# cpu_nand.net
KiCad netlist of a schematic drawn in Altium Designer
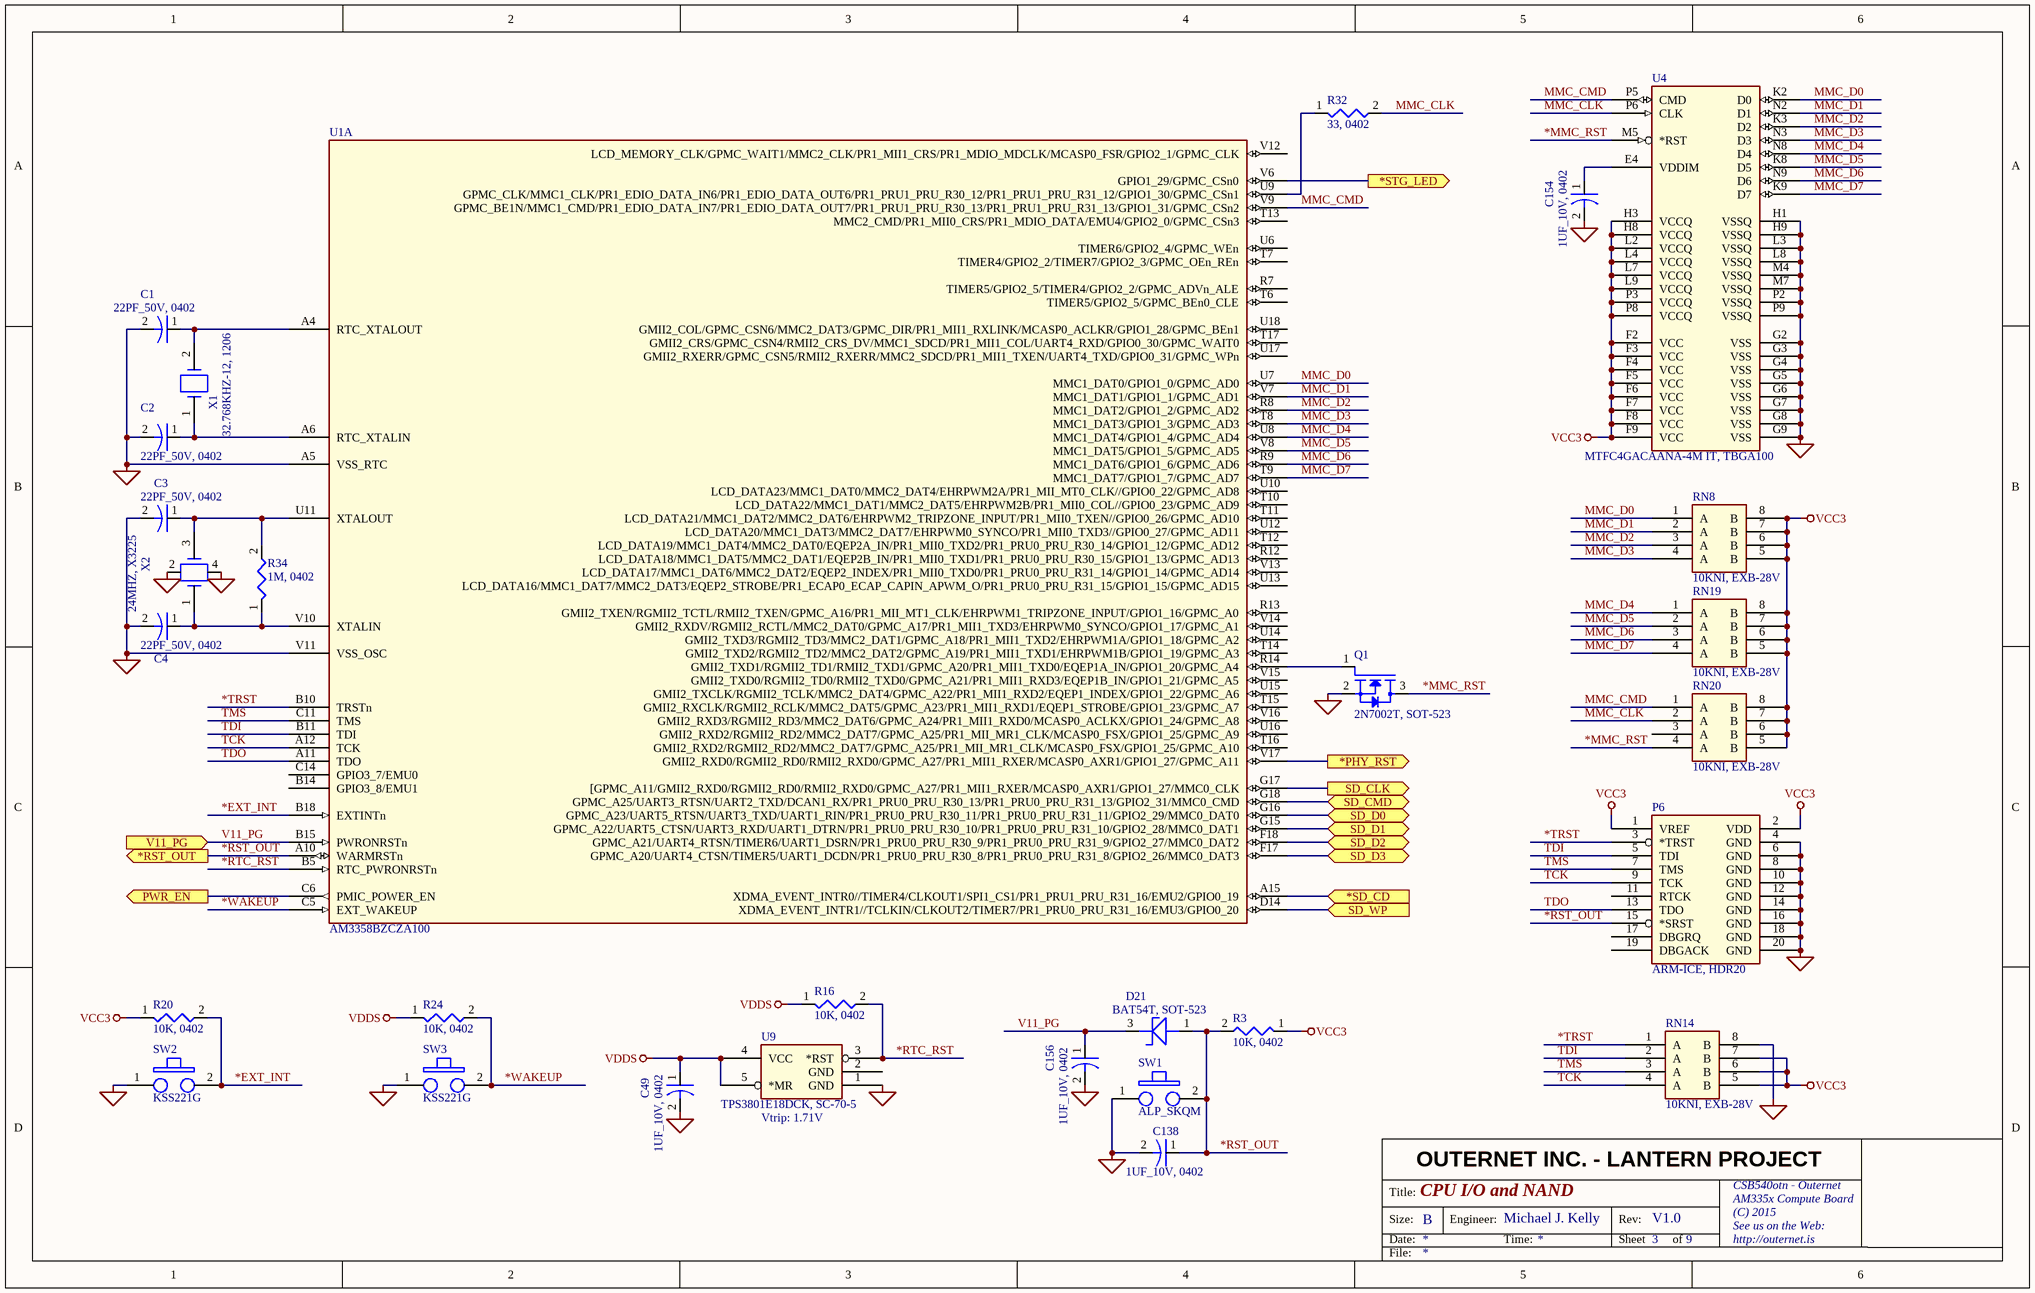
[diagram p0: cpu_nand.SchDoc]

(export (version "E")
  (design (tool "Eeschema 10.0.6"))
  (components
    (comp (ref "C1")
      (value "22PF_50V, 0402")
      (footprint "0402C")
      (description "CAP - 0402 PKG")
      (libsource (lib "COGENT_Library") (part "22PF_50V, 0402"))
    )
    (comp (ref "C2")
      (value "22PF_50V, 0402")
      (footprint "0402C")
      (description "CAP - 0402 PKG")
      (libsource (lib "COGENT_Library") (part "22PF_50V, 0402"))
    )
    (comp (ref "C3")
      (value "22PF_50V, 0402")
      (footprint "0402C")
      (description "CAP - 0402 PKG")
      (libsource (lib "COGENT_Library") (part "22PF_50V, 0402"))
    )
    (comp (ref "C4")
      (value "22PF_50V, 0402")
      (footprint "0402C")
      (description "CAP - 0402 PKG")
      (libsource (lib "COGENT_Library") (part "22PF_50V, 0402"))
    )
    (comp (ref "C49")
      (value "1UF_10V, 0402")
      (footprint "0402C")
      (description "CAP - 0402 PKG")
      (libsource (lib "COGENT_Library") (part "1UF_10V, 0402"))
    )
    (comp (ref "C138")
      (value "1UF_10V, 0402")
      (footprint "0402C")
      (description "CAP - 0402 PKG")
      (libsource (lib "COGENT_Library") (part "1UF_10V, 0402"))
    )
    (comp (ref "C154")
      (value "1UF_10V, 0402")
      (footprint "0402C")
      (description "CAP - 0402 PKG")
      (libsource (lib "COGENT_Library") (part "1UF_10V, 0402"))
    )
    (comp (ref "C156")
      (value "1UF_10V, 0402")
      (footprint "0402C")
      (description "CAP - 0402 PKG")
      (libsource (lib "COGENT_Library") (part "1UF_10V, 0402"))
    )
    (comp (ref "D21")
      (value "BAT54T, SOT-523")
      (footprint "SOT-523")
      (description "DIODE - SCHOTTKY, 30V, 200MA")
      (libsource (lib "COGENT_Library") (part "BAT54T, SOT-523"))
    )
    (comp (ref "P6")
      (value "ARM-ICE, HDR20")
      (footprint "HDR20")
      (description "CONN - ARM JTAG CONNECTOR")
      (libsource (lib "COGENT_Library") (part "ARM-ICE, HDR20"))
    )
    (comp (ref "Q1")
      (value "2N7002T, SOT-523")
      (footprint "SOT-523")
      (description "N-FET - 60V, 500ma @ 10V, Vgs(th) 2V")
      (libsource (lib "COGENT_Library") (part "2N7002T, SOT-523"))
    )
    (comp (ref "R3")
      (value "10K, 0402")
      (footprint "0402R")
      (description "RES - 0402 PKG")
      (libsource (lib "COGENT_Library") (part "10K, 0402"))
    )
    (comp (ref "R16")
      (value "10K, 0402")
      (footprint "0402R")
      (description "RES - 0402 PKG")
      (libsource (lib "COGENT_Library") (part "10K, 0402"))
    )
    (comp (ref "R20")
      (value "10K, 0402")
      (footprint "0402R")
      (description "RES - 0402 PKG")
      (libsource (lib "COGENT_Library") (part "10K, 0402"))
    )
    (comp (ref "R24")
      (value "10K, 0402")
      (footprint "0402R")
      (description "RES - 0402 PKG")
      (libsource (lib "COGENT_Library") (part "10K, 0402"))
    )
    (comp (ref "R32")
      (value "33, 0402")
      (footprint "0402R")
      (description "RES - 0402 PKG")
      (libsource (lib "COGENT_Library") (part "33, 0402"))
    )
    (comp (ref "R34")
      (value "1M, 0402")
      (footprint "0402R")
      (description "RES - 0402 PKG")
      (libsource (lib "COGENT_Library") (part "1M, 0402"))
    )
    (comp (ref "RN8")
      (value "10KNI, EXB-28V")
      (footprint "EXB-28V")
      (description "RES NET, 4 INDIVIDUAL, EXB-28V")
      (libsource (lib "COGENT_Library") (part "10KNI, EXB-28V"))
    )
    (comp (ref "RN14")
      (value "10KNI, EXB-28V")
      (footprint "EXB-28V")
      (description "RES NET, 4 INDIVIDUAL, EXB-28V")
      (libsource (lib "COGENT_Library") (part "10KNI, EXB-28V"))
    )
    (comp (ref "RN19")
      (value "10KNI, EXB-28V")
      (footprint "EXB-28V")
      (description "RES NET, 4 INDIVIDUAL, EXB-28V")
      (libsource (lib "COGENT_Library") (part "10KNI, EXB-28V"))
    )
    (comp (ref "RN20")
      (value "10KNI, EXB-28V")
      (footprint "EXB-28V")
      (description "RES NET, 4 INDIVIDUAL, EXB-28V")
      (libsource (lib "COGENT_Library") (part "10KNI, EXB-28V"))
    )
    (comp (ref "SW1")
      (value "ALP_SKQM")
      (footprint "ALPS_SKQM")
      (description "SWITCH - PUSHBUTTON SMT, 6MM X 3.5MM")
      (libsource (lib "COGENT_Library") (part "ALP_SKQM"))
    )
    (comp (ref "SW2")
      (value "KSS221G")
      (footprint "KSS221G")
      (description "SWITCH - PUSHBUTTON SMT, SIDE ACTUATED")
      (libsource (lib "COGENT_Library") (part "KSS221G"))
    )
    (comp (ref "SW3")
      (value "KSS221G")
      (footprint "KSS221G")
      (description "SWITCH - PUSHBUTTON SMT, SIDE ACTUATED")
      (libsource (lib "COGENT_Library") (part "KSS221G"))
    )
    (comp (ref "U1")
      (value "AM3358BZCZA100")
      (footprint "BGA324x18")
      (description "MPU - CORTEX-A8 CORE, SDIO, GIGe, USB x2, UART x3, CAN, 2D/3D")
      (libsource (lib "COGENT_Library") (part "AM3358BZCZA100"))
    )
    (comp (ref "U4")
      (value "MTFC4GACAANA-4M IT, TBGA100")
      (footprint "TBGA100")
      (description "NAND FLASH - eMMC 4GB/8GB")
      (libsource (lib "COGENT_Library") (part "MTFC4GACAANA-4M IT, TBGA100"))
    )
    (comp (ref "U9")
      (value "TPS3801E18DCK, SC-70-5")
      (footprint "SOT-353/SC-70-5")
      (description "IC - RESET, 1.71V, 200MSEC, MR INPUT, OPEN DRAIN OUTPUT")
      (fields (field (name "VTRIP") "1.71V"))
      (libsource (lib "COGENT_Library") (part "TPS3801E18DCK, SC-70-5"))
    )
    (comp (ref "X1")
      (value "32.768KHZ-12, 1206")
      (footprint "1206X")
      (description "CRYSTAL - SMT, 1206, 12.5PF, ABS07 PKG")
      (libsource (lib "COGENT_Library") (part "32.768KHZ-12, 1206"))
    )
    (comp (ref "X2")
      (value "24MHZ, X3225")
      (footprint "X3225")
      (description "CRYSTAL - SMT, 3.2MM x 2.5MM, ABM8 PKG")
      (libsource (lib "COGENT_Library") (part "24MHZ, X3225"))
    )
  )
  (nets
    (net (code "1") (name "/*EXT_INT") (class "Default")
      (node (ref "R20") (pin "2") (pinfunction "2_2") (pintype "passive"))
      (node (ref "SW2") (pin "2") (pinfunction "2_2") (pintype "passive"))
      (node (ref "U1") (pin "B18") (pinfunction "EXTINTn_B18") (pintype "input"))
    )
    (net (code "2") (name "/*MMC_RST") (class "Default")
      (node (ref "Q1") (pin "3") (pinfunction "DRAIN_3") (pintype "passive"))
      (node (ref "RN20") (pin "4") (pinfunction "A_4") (pintype "passive"))
      (node (ref "U4") (pin "M5") (pinfunction "*RST_M5") (pintype "input"))
    )
    (net (code "3") (name "/*PHY_RST") (class "Default")
      (node (ref "U1") (pin "V17") (pinfunction "GMII2_RXD0/RGMII2_RD0/RMII2_RXD0/GPMC_A27/PR1_MII1_RXER/MCASP0_AXR1/GPIO1_27/GPMC_A11_V17") (pintype "bidirectional"))
    )
    (net (code "4") (name "/*RST_OUT") (class "Default")
      (node (ref "C138") (pin "1") (pinfunction "1_1") (pintype "passive"))
      (node (ref "D21") (pin "1") (pinfunction "ANODE_1") (pintype "passive"))
      (node (ref "P6") (pin "15") (pinfunction "*SRST_15") (pintype "passive"))
      (node (ref "R3") (pin "2") (pinfunction "2_2") (pintype "passive"))
      (node (ref "SW1") (pin "2") (pinfunction "2_2") (pintype "passive"))
      (node (ref "U1") (pin "A10") (pinfunction "WARMRSTn_A10") (pintype "bidirectional"))
    )
    (net (code "5") (name "/*RTC_RST") (class "Default")
      (node (ref "R16") (pin "2") (pinfunction "2_2") (pintype "passive"))
      (node (ref "U1") (pin "B5") (pinfunction "RTC_PWRONRSTn_B5") (pintype "input"))
      (node (ref "U9") (pin "3") (pinfunction "*RST_3") (pintype "open_collector"))
    )
    (net (code "6") (name "/*SD_CD") (class "Default")
      (node (ref "U1") (pin "A15") (pinfunction "XDMA_EVENT_INTR0//TIMER4/CLKOUT1/SPI1_CS1/PR1_PRU1_PRU_R31_16/EMU2/GPIO0_19_A15") (pintype "bidirectional"))
    )
    (net (code "7") (name "/*STG_LED") (class "Default")
      (node (ref "U1") (pin "V6") (pinfunction "GPIO1_29/GPMC_CSn0_V6") (pintype "bidirectional"))
    )
    (net (code "8") (name "/*TRST") (class "Default")
      (node (ref "P6") (pin "3") (pinfunction "*TRST_3") (pintype "passive"))
      (node (ref "RN14") (pin "1") (pinfunction "A_1") (pintype "passive"))
      (node (ref "U1") (pin "B10") (pinfunction "TRSTn_B10") (pintype "passive"))
    )
    (net (code "9") (name "/*WAKEUP") (class "Default")
      (node (ref "R24") (pin "2") (pinfunction "2_2") (pintype "passive"))
      (node (ref "SW3") (pin "2") (pinfunction "2_2") (pintype "passive"))
      (node (ref "U1") (pin "C5") (pinfunction "EXT_WAKEUP_C5") (pintype "input"))
    )
    (net (code "10") (name "/MMC_CLK") (class "Default")
      (node (ref "R32") (pin "2") (pinfunction "2_2") (pintype "passive"))
      (node (ref "RN20") (pin "2") (pinfunction "A_2") (pintype "passive"))
      (node (ref "U4") (pin "P6") (pinfunction "CLK_P6") (pintype "input"))
    )
    (net (code "11") (name "/MMC_CMD") (class "Default")
      (node (ref "RN20") (pin "1") (pinfunction "A_1") (pintype "passive"))
      (node (ref "U1") (pin "V9") (pinfunction "GPMC_BE1N/MMC1_CMD/PR1_EDIO_DATA_IN7/PR1_EDIO_DATA_OUT7/PR1_PRU1_PRU_R30_13/PR1_PRU1_PRU_R31_13/GPIO1_31/GPMC_CSn2_V9") (pintype "bidirectional"))
      (node (ref "U4") (pin "P5") (pinfunction "CMD_P5") (pintype "bidirectional"))
    )
    (net (code "12") (name "/MMC_D0") (class "Default")
      (node (ref "RN8") (pin "1") (pinfunction "A_1") (pintype "passive"))
      (node (ref "U1") (pin "U7") (pinfunction "MMC1_DAT0/GPIO1_0/GPMC_AD0_U7") (pintype "bidirectional"))
      (node (ref "U4") (pin "K2") (pinfunction "D0_K2") (pintype "bidirectional"))
    )
    (net (code "13") (name "/MMC_D1") (class "Default")
      (node (ref "RN8") (pin "2") (pinfunction "A_2") (pintype "passive"))
      (node (ref "U1") (pin "V7") (pinfunction "MMC1_DAT1/GPIO1_1/GPMC_AD1_V7") (pintype "bidirectional"))
      (node (ref "U4") (pin "N2") (pinfunction "D1_N2") (pintype "bidirectional"))
    )
    (net (code "14") (name "/MMC_D2") (class "Default")
      (node (ref "RN8") (pin "3") (pinfunction "A_3") (pintype "passive"))
      (node (ref "U1") (pin "R8") (pinfunction "MMC1_DAT2/GPIO1_2/GPMC_AD2_R8") (pintype "bidirectional"))
      (node (ref "U4") (pin "K3") (pinfunction "D2_K3") (pintype "bidirectional"))
    )
    (net (code "15") (name "/MMC_D3") (class "Default")
      (node (ref "RN8") (pin "4") (pinfunction "A_4") (pintype "passive"))
      (node (ref "U1") (pin "T8") (pinfunction "MMC1_DAT3/GPIO1_3/GPMC_AD3_T8") (pintype "bidirectional"))
      (node (ref "U4") (pin "N3") (pinfunction "D3_N3") (pintype "bidirectional"))
    )
    (net (code "16") (name "/MMC_D4") (class "Default")
      (node (ref "RN19") (pin "1") (pinfunction "A_1") (pintype "passive"))
      (node (ref "U1") (pin "U8") (pinfunction "MMC1_DAT4/GPIO1_4/GPMC_AD4_U8") (pintype "bidirectional"))
      (node (ref "U4") (pin "N8") (pinfunction "D4_N8") (pintype "bidirectional"))
    )
    (net (code "17") (name "/MMC_D5") (class "Default")
      (node (ref "RN19") (pin "2") (pinfunction "A_2") (pintype "passive"))
      (node (ref "U1") (pin "V8") (pinfunction "MMC1_DAT5/GPIO1_5/GPMC_AD5_V8") (pintype "bidirectional"))
      (node (ref "U4") (pin "K8") (pinfunction "D5_K8") (pintype "bidirectional"))
    )
    (net (code "18") (name "/MMC_D6") (class "Default")
      (node (ref "RN19") (pin "3") (pinfunction "A_3") (pintype "passive"))
      (node (ref "U1") (pin "R9") (pinfunction "MMC1_DAT6/GPIO1_6/GPMC_AD6_R9") (pintype "bidirectional"))
      (node (ref "U4") (pin "N9") (pinfunction "D6_N9") (pintype "bidirectional"))
    )
    (net (code "19") (name "/MMC_D7") (class "Default")
      (node (ref "RN19") (pin "4") (pinfunction "A_4") (pintype "passive"))
      (node (ref "U1") (pin "T9") (pinfunction "MMC1_DAT7/GPIO1_7/GPMC_AD7_T9") (pintype "bidirectional"))
      (node (ref "U4") (pin "K9") (pinfunction "D7_K9") (pintype "bidirectional"))
    )
    (net (code "20") (name "/PWR_EN") (class "Default")
      (node (ref "U1") (pin "C6") (pinfunction "PMIC_POWER_EN_C6") (pintype "output"))
    )
    (net (code "21") (name "/SD_CLK") (class "Default")
      (node (ref "U1") (pin "G17") (pinfunction "[GPMC_A11/GMII2_RXD0/RGMII2_RD0/RMII2_RXD0/GPMC_A27/PR1_MII1_RXER/MCASP0_AXR1/GPIO1_27/MMC0_CLK_G17") (pintype "bidirectional"))
    )
    (net (code "22") (name "/SD_CMD") (class "Default")
      (node (ref "U1") (pin "G18") (pinfunction "GPMC_A25/UART3_RTSN/UART2_TXD/DCAN1_RX/PR1_PRU0_PRU_R30_13/PR1_PRU0_PRU_R31_13/GPIO2_31/MMC0_CMD_G18") (pintype "bidirectional"))
    )
    (net (code "23") (name "/SD_D0") (class "Default")
      (node (ref "U1") (pin "G16") (pinfunction "GPMC_A23/UART5_RTSN/UART3_TXD/UART1_RIN/PR1_PRU0_PRU_R30_11/PR1_PRU0_PRU_R31_11/GPIO2_29/MMC0_DAT0_G16") (pintype "bidirectional"))
    )
    (net (code "24") (name "/SD_D1") (class "Default")
      (node (ref "U1") (pin "G15") (pinfunction "GPMC_A22/UART5_CTSN/UART3_RXD/UART1_DTRN/PR1_PRU0_PRU_R30_10/PR1_PRU0_PRU_R31_10/GPIO2_28/MMC0_DAT1_G15") (pintype "bidirectional"))
    )
    (net (code "25") (name "/SD_D2") (class "Default")
      (node (ref "U1") (pin "F18") (pinfunction "GPMC_A21/UART4_RTSN/TIMER6/UART1_DSRN/PR1_PRU0_PRU_R30_9/PR1_PRU0_PRU_R31_9/GPIO2_27/MMC0_DAT2_F18") (pintype "bidirectional"))
    )
    (net (code "26") (name "/SD_D3") (class "Default")
      (node (ref "U1") (pin "F17") (pinfunction "GPMC_A20/UART4_CTSN/TIMER5/UART1_DCDN/PR1_PRU0_PRU_R30_8/PR1_PRU0_PRU_R31_8/GPIO2_26/MMC0_DAT3_F17") (pintype "bidirectional"))
    )
    (net (code "27") (name "/SD_WP") (class "Default")
      (node (ref "U1") (pin "D14") (pinfunction "XDMA_EVENT_INTR1//TCLKIN/CLKOUT2/TIMER7/PR1_PRU0_PRU_R31_16/EMU3/GPIO0_20_D14") (pintype "bidirectional"))
    )
    (net (code "28") (name "/TCK") (class "Default")
      (node (ref "P6") (pin "9") (pinfunction "TCK_9") (pintype "passive"))
      (node (ref "RN14") (pin "4") (pinfunction "A_4") (pintype "passive"))
      (node (ref "U1") (pin "A12") (pinfunction "TCK_A12") (pintype "passive"))
    )
    (net (code "29") (name "/TDI") (class "Default")
      (node (ref "P6") (pin "5") (pinfunction "TDI_5") (pintype "passive"))
      (node (ref "RN14") (pin "2") (pinfunction "A_2") (pintype "passive"))
      (node (ref "U1") (pin "B11") (pinfunction "TDI_B11") (pintype "passive"))
    )
    (net (code "30") (name "/TDO") (class "Default")
      (node (ref "P6") (pin "13") (pinfunction "TDO_13") (pintype "passive"))
      (node (ref "U1") (pin "A11") (pinfunction "TDO_A11") (pintype "passive"))
    )
    (net (code "31") (name "/TMS") (class "Default")
      (node (ref "P6") (pin "7") (pinfunction "TMS_7") (pintype "passive"))
      (node (ref "RN14") (pin "3") (pinfunction "A_3") (pintype "passive"))
      (node (ref "U1") (pin "C11") (pinfunction "TMS_C11") (pintype "passive"))
    )
    (net (code "32") (name "/V11_PG") (class "Default")
      (node (ref "C156") (pin "1") (pinfunction "1_1") (pintype "passive"))
      (node (ref "D21") (pin "3") (pinfunction "CATHODE_3") (pintype "passive"))
      (node (ref "U1") (pin "B15") (pinfunction "PWRONRSTn_B15") (pintype "input"))
    )
    (net (code "33") (name "GND") (class "Default")
      (node (ref "C1") (pin "2") (pinfunction "2_2") (pintype "passive"))
      (node (ref "C138") (pin "2") (pinfunction "2_2") (pintype "passive"))
      (node (ref "C154") (pin "2") (pinfunction "2_2") (pintype "passive"))
      (node (ref "C156") (pin "2") (pinfunction "2_2") (pintype "passive"))
      (node (ref "C2") (pin "2") (pinfunction "2_2") (pintype "passive"))
      (node (ref "C3") (pin "2") (pinfunction "2_2") (pintype "passive"))
      (node (ref "C4") (pin "2") (pinfunction "2_2") (pintype "passive"))
      (node (ref "C49") (pin "2") (pinfunction "2_2") (pintype "passive"))
      (node (ref "P6") (pin "10") (pinfunction "GND_10") (pintype "passive"))
      (node (ref "P6") (pin "12") (pinfunction "GND_12") (pintype "passive"))
      (node (ref "P6") (pin "14") (pinfunction "GND_14") (pintype "passive"))
      (node (ref "P6") (pin "16") (pinfunction "GND_16") (pintype "passive"))
      (node (ref "P6") (pin "18") (pinfunction "GND_18") (pintype "passive"))
      (node (ref "P6") (pin "20") (pinfunction "GND_20") (pintype "passive"))
      (node (ref "P6") (pin "4") (pinfunction "GND_4") (pintype "passive"))
      (node (ref "P6") (pin "6") (pinfunction "GND_6") (pintype "passive"))
      (node (ref "P6") (pin "8") (pinfunction "GND_8") (pintype "passive"))
      (node (ref "Q1") (pin "2") (pinfunction "SOURCE_2") (pintype "passive"))
      (node (ref "RN14") (pin "8") (pinfunction "B_8") (pintype "passive"))
      (node (ref "SW1") (pin "1") (pinfunction "1_1") (pintype "passive"))
      (node (ref "SW2") (pin "1") (pinfunction "1_1") (pintype "passive"))
      (node (ref "SW3") (pin "1") (pinfunction "1_1") (pintype "passive"))
      (node (ref "U1") (pin "A5") (pinfunction "VSS_RTC_A5") (pintype "power_in"))
      (node (ref "U1") (pin "V11") (pinfunction "VSS_OSC_V11") (pintype "power_in"))
      (node (ref "U4") (pin "G2") (pinfunction "VSS_G2") (pintype "power_in"))
      (node (ref "U4") (pin "G3") (pinfunction "VSS_G3") (pintype "power_in"))
      (node (ref "U4") (pin "G4") (pinfunction "VSS_G4") (pintype "power_in"))
      (node (ref "U4") (pin "G5") (pinfunction "VSS_G5") (pintype "power_in"))
      (node (ref "U4") (pin "G6") (pinfunction "VSS_G6") (pintype "power_in"))
      (node (ref "U4") (pin "G7") (pinfunction "VSS_G7") (pintype "power_in"))
      (node (ref "U4") (pin "G8") (pinfunction "VSS_G8") (pintype "power_in"))
      (node (ref "U4") (pin "G9") (pinfunction "VSS_G9") (pintype "power_in"))
      (node (ref "U4") (pin "H1") (pinfunction "VSSQ_H1") (pintype "power_in"))
      (node (ref "U4") (pin "H9") (pinfunction "VSSQ_H9") (pintype "power_in"))
      (node (ref "U4") (pin "L3") (pinfunction "VSSQ_L3") (pintype "power_in"))
      (node (ref "U4") (pin "L8") (pinfunction "VSSQ_L8") (pintype "power_in"))
      (node (ref "U4") (pin "M4") (pinfunction "VSSQ_M4") (pintype "power_in"))
      (node (ref "U4") (pin "M7") (pinfunction "VSSQ_M7") (pintype "power_in"))
      (node (ref "U4") (pin "P2") (pinfunction "VSSQ_P2") (pintype "power_in"))
      (node (ref "U4") (pin "P9") (pinfunction "VSSQ_P9") (pintype "power_in"))
      (node (ref "U9") (pin "1") (pinfunction "GND_1") (pintype "power_in"))
      (node (ref "X2") (pin "2") (pinfunction "2_2") (pintype "passive"))
      (node (ref "X2") (pin "4") (pinfunction "4_4") (pintype "passive"))
    )
    (net (code "34") (name "Net-(Q1-GATE)") (class "Default")
      (node (ref "Q1") (pin "1") (pinfunction "GATE_1") (pintype "passive"))
      (node (ref "U1") (pin "R14") (pinfunction "GMII2_TXD1/RGMII2_TD1/RMII2_TXD1/GPMC_A20/PR1_MII1_TXD0/EQEP1A_IN/GPIO1_20/GPMC_A4_R14") (pintype "bidirectional"))
    )
    (net (code "35") (name "Net-(U1A-GPMC_CLK{slash}MMC1_CLK{slash}PR1_EDIO_DATA_IN6{slash}PR1_EDIO_DATA_OUT6{slash}PR1_PRU1_PRU_R30_12{slash}PR1_PRU1_PRU_R31_12{slash}GPIO1_30{slash}GPMC_CSn1)") (class "Default")
      (node (ref "R32") (pin "1") (pinfunction "1_1") (pintype "passive"))
      (node (ref "U1") (pin "U9") (pinfunction "GPMC_CLK/MMC1_CLK/PR1_EDIO_DATA_IN6/PR1_EDIO_DATA_OUT6/PR1_PRU1_PRU_R30_12/PR1_PRU1_PRU_R31_12/GPIO1_30/GPMC_CSn1_U9") (pintype "bidirectional"))
    )
    (net (code "36") (name "Net-(U1A-RTC_XTALIN)") (class "Default")
      (node (ref "C2") (pin "1") (pinfunction "1_1") (pintype "passive"))
      (node (ref "U1") (pin "A6") (pinfunction "RTC_XTALIN_A6") (pintype "passive"))
      (node (ref "X1") (pin "1") (pinfunction "1_1") (pintype "passive"))
    )
    (net (code "37") (name "Net-(U1A-RTC_XTALOUT)") (class "Default")
      (node (ref "C1") (pin "1") (pinfunction "1_1") (pintype "passive"))
      (node (ref "U1") (pin "A4") (pinfunction "RTC_XTALOUT_A4") (pintype "passive"))
      (node (ref "X1") (pin "2") (pinfunction "2_2") (pintype "passive"))
    )
    (net (code "38") (name "Net-(U1A-XTALIN)") (class "Default")
      (node (ref "C4") (pin "1") (pinfunction "1_1") (pintype "passive"))
      (node (ref "R34") (pin "1") (pinfunction "1_1") (pintype "passive"))
      (node (ref "U1") (pin "V10") (pinfunction "XTALIN_V10") (pintype "passive"))
      (node (ref "X2") (pin "1") (pinfunction "1_1") (pintype "passive"))
    )
    (net (code "39") (name "Net-(U1A-XTALOUT)") (class "Default")
      (node (ref "C3") (pin "1") (pinfunction "1_1") (pintype "passive"))
      (node (ref "R34") (pin "2") (pinfunction "2_2") (pintype "passive"))
      (node (ref "U1") (pin "U11") (pinfunction "XTALOUT_U11") (pintype "passive"))
      (node (ref "X2") (pin "3") (pinfunction "3_3") (pintype "passive"))
    )
    (net (code "40") (name "Net-(U4-VDDIM)") (class "Default")
      (node (ref "C154") (pin "1") (pinfunction "1_1") (pintype "passive"))
      (node (ref "U4") (pin "E4") (pinfunction "VDDIM_E4") (pintype "power_in"))
    )
    (net (code "41") (name "VCC3") (class "Default")
      (node (ref "P6") (pin "1") (pinfunction "VREF_1") (pintype "passive"))
      (node (ref "P6") (pin "2") (pinfunction "VDD_2") (pintype "passive"))
      (node (ref "R20") (pin "1") (pinfunction "1_1") (pintype "passive"))
      (node (ref "R3") (pin "1") (pinfunction "1_1") (pintype "passive"))
      (node (ref "RN14") (pin "5") (pinfunction "B_5") (pintype "passive"))
      (node (ref "RN14") (pin "6") (pinfunction "B_6") (pintype "passive"))
      (node (ref "RN14") (pin "7") (pinfunction "B_7") (pintype "passive"))
      (node (ref "RN19") (pin "5") (pinfunction "B_5") (pintype "passive"))
      (node (ref "RN19") (pin "6") (pinfunction "B_6") (pintype "passive"))
      (node (ref "RN19") (pin "7") (pinfunction "B_7") (pintype "passive"))
      (node (ref "RN19") (pin "8") (pinfunction "B_8") (pintype "passive"))
      (node (ref "RN20") (pin "5") (pinfunction "B_5") (pintype "passive"))
      (node (ref "RN20") (pin "6") (pinfunction "B_6") (pintype "passive"))
      (node (ref "RN20") (pin "7") (pinfunction "B_7") (pintype "passive"))
      (node (ref "RN20") (pin "8") (pinfunction "B_8") (pintype "passive"))
      (node (ref "RN8") (pin "5") (pinfunction "B_5") (pintype "passive"))
      (node (ref "RN8") (pin "6") (pinfunction "B_6") (pintype "passive"))
      (node (ref "RN8") (pin "7") (pinfunction "B_7") (pintype "passive"))
      (node (ref "RN8") (pin "8") (pinfunction "B_8") (pintype "passive"))
      (node (ref "U4") (pin "F2") (pinfunction "VCC_F2") (pintype "power_in"))
      (node (ref "U4") (pin "F3") (pinfunction "VCC_F3") (pintype "power_in"))
      (node (ref "U4") (pin "F4") (pinfunction "VCC_F4") (pintype "power_in"))
      (node (ref "U4") (pin "F5") (pinfunction "VCC_F5") (pintype "power_in"))
      (node (ref "U4") (pin "F6") (pinfunction "VCC_F6") (pintype "power_in"))
      (node (ref "U4") (pin "F7") (pinfunction "VCC_F7") (pintype "power_in"))
      (node (ref "U4") (pin "F8") (pinfunction "VCC_F8") (pintype "power_in"))
      (node (ref "U4") (pin "F9") (pinfunction "VCC_F9") (pintype "power_in"))
      (node (ref "U4") (pin "H3") (pinfunction "VCCQ_H3") (pintype "power_in"))
      (node (ref "U4") (pin "H8") (pinfunction "VCCQ_H8") (pintype "power_in"))
      (node (ref "U4") (pin "L2") (pinfunction "VCCQ_L2") (pintype "power_in"))
      (node (ref "U4") (pin "L4") (pinfunction "VCCQ_L4") (pintype "power_in"))
      (node (ref "U4") (pin "L7") (pinfunction "VCCQ_L7") (pintype "power_in"))
      (node (ref "U4") (pin "L9") (pinfunction "VCCQ_L9") (pintype "power_in"))
      (node (ref "U4") (pin "P3") (pinfunction "VCCQ_P3") (pintype "power_in"))
      (node (ref "U4") (pin "P8") (pinfunction "VCCQ_P8") (pintype "power_in"))
    )
    (net (code "42") (name "VDDS") (class "Default")
      (node (ref "C49") (pin "1") (pinfunction "1_1") (pintype "passive"))
      (node (ref "R16") (pin "1") (pinfunction "1_1") (pintype "passive"))
      (node (ref "R24") (pin "1") (pinfunction "1_1") (pintype "passive"))
      (node (ref "U9") (pin "4") (pinfunction "VCC_4") (pintype "power_in"))
      (node (ref "U9") (pin "5") (pinfunction "*MR_5") (pintype "passive"))
    )
    (net (code "43") (name "unconnected-(P6-DBGACK-Pad19)") (class "Default")
      (node (ref "P6") (pin "19") (pinfunction "DBGACK_19") (pintype "passive"))
    )
    (net (code "44") (name "unconnected-(P6-DBGRQ-Pad17)") (class "Default")
      (node (ref "P6") (pin "17") (pinfunction "DBGRQ_17") (pintype "passive"))
    )
    (net (code "45") (name "unconnected-(P6-RTCK-Pad11)") (class "Default")
      (node (ref "P6") (pin "11") (pinfunction "RTCK_11") (pintype "passive"))
    )
    (net (code "46") (name "unconnected-(RN20-A-Pad3)") (class "Default")
      (node (ref "RN20") (pin "3") (pinfunction "A_3") (pintype "passive"))
    )
    (net (code "47") (name "unconnected-(U1A-GMII2_COL{slash}GPMC_CSN6{slash}MMC2_DAT3{slash}GPMC_DIR{slash}PR1_MII1_RXLINK{slash}MCASP0_ACLKR{slash}GPIO1_28{slash}GPMC_BEn1-PadU18)") (class "Default")
      (node (ref "U1") (pin "U18") (pinfunction "GMII2_COL/GPMC_CSN6/MMC2_DAT3/GPMC_DIR/PR1_MII1_RXLINK/MCASP0_ACLKR/GPIO1_28/GPMC_BEn1_U18") (pintype "bidirectional"))
    )
    (net (code "48") (name "unconnected-(U1A-GMII2_CRS{slash}GPMC_CSN4{slash}RMII2_CRS_DV{slash}MMC1_SDCD{slash}PR1_MII1_COL{slash}UART4_RXD{slash}GPIO0_30{slash}GPMC_WAIT0-PadT17)") (class "Default")
      (node (ref "U1") (pin "T17") (pinfunction "GMII2_CRS/GPMC_CSN4/RMII2_CRS_DV/MMC1_SDCD/PR1_MII1_COL/UART4_RXD/GPIO0_30/GPMC_WAIT0_T17") (pintype "bidirectional"))
    )
    (net (code "49") (name "unconnected-(U1A-GMII2_RXCLK{slash}RGMII2_RCLK{slash}MMC2_DAT5{slash}GPMC_A23{slash}PR1_MII1_RXD1{slash}EQEP1_STROBE{slash}GPIO1_23{slash}GPMC_A7-PadT15)") (class "Default")
      (node (ref "U1") (pin "T15") (pinfunction "GMII2_RXCLK/RGMII2_RCLK/MMC2_DAT5/GPMC_A23/PR1_MII1_RXD1/EQEP1_STROBE/GPIO1_23/GPMC_A7_T15") (pintype "bidirectional"))
    )
    (net (code "50") (name "unconnected-(U1A-GMII2_RXD2{slash}RGMII2_RD2{slash}MMC2_DAT7{slash}GPMC_A25{slash}PR1_MII_MR1_CLK{slash}MCASP0_FSX{slash}GPIO1_25{slash}GPMC_A9-PadU16)") (class "Default")
      (node (ref "U1") (pin "U16") (pinfunction "GMII2_RXD2/RGMII2_RD2/MMC2_DAT7/GPMC_A25/PR1_MII_MR1_CLK/MCASP0_FSX/GPIO1_25/GPMC_A9_U16") (pintype "bidirectional"))
    )
    (net (code "51") (name "unconnected-(U1A-GMII2_RXD2{slash}RGMII2_RD2{slash}MMC2_DAT7{slash}GPMC_A25{slash}PR1_MII_MR1_CLK{slash}MCASP0_FSX{slash}GPIO1_25{slash}GPMC_A10-PadT16)") (class "Default")
      (node (ref "U1") (pin "T16") (pinfunction "GMII2_RXD2/RGMII2_RD2/MMC2_DAT7/GPMC_A25/PR1_MII_MR1_CLK/MCASP0_FSX/GPIO1_25/GPMC_A10_T16") (pintype "bidirectional"))
    )
    (net (code "52") (name "unconnected-(U1A-GMII2_RXD3{slash}RGMII2_RD3{slash}MMC2_DAT6{slash}GPMC_A24{slash}PR1_MII1_RXD0{slash}MCASP0_ACLKX{slash}GPIO1_24{slash}GPMC_A8-PadV16)") (class "Default")
      (node (ref "U1") (pin "V16") (pinfunction "GMII2_RXD3/RGMII2_RD3/MMC2_DAT6/GPMC_A24/PR1_MII1_RXD0/MCASP0_ACLKX/GPIO1_24/GPMC_A8_V16") (pintype "bidirectional"))
    )
    (net (code "53") (name "unconnected-(U1A-GMII2_RXDV{slash}RGMII2_RCTL{slash}MMC2_DAT0{slash}GPMC_A17{slash}PR1_MII1_TXD3{slash}EHRPWM0_SYNCO{slash}GPIO1_17{slash}GPMC_A1-PadV14)") (class "Default")
      (node (ref "U1") (pin "V14") (pinfunction "GMII2_RXDV/RGMII2_RCTL/MMC2_DAT0/GPMC_A17/PR1_MII1_TXD3/EHRPWM0_SYNCO/GPIO1_17/GPMC_A1_V14") (pintype "bidirectional"))
    )
    (net (code "54") (name "unconnected-(U1A-GMII2_RXERR{slash}GPMC_CSN5{slash}RMII2_RXERR{slash}MMC2_SDCD{slash}PR1_MII1_TXEN{slash}UART4_TXD{slash}GPIO0_31{slash}GPMC_WPn-PadU17)") (class "Default")
      (node (ref "U1") (pin "U17") (pinfunction "GMII2_RXERR/GPMC_CSN5/RMII2_RXERR/MMC2_SDCD/PR1_MII1_TXEN/UART4_TXD/GPIO0_31/GPMC_WPn_U17") (pintype "bidirectional"))
    )
    (net (code "55") (name "unconnected-(U1A-GMII2_TXCLK{slash}RGMII2_TCLK{slash}MMC2_DAT4{slash}GPMC_A22{slash}PR1_MII1_RXD2{slash}EQEP1_INDEX{slash}GPIO1_22{slash}GPMC_A6-PadU15)") (class "Default")
      (node (ref "U1") (pin "U15") (pinfunction "GMII2_TXCLK/RGMII2_TCLK/MMC2_DAT4/GPMC_A22/PR1_MII1_RXD2/EQEP1_INDEX/GPIO1_22/GPMC_A6_U15") (pintype "bidirectional"))
    )
    (net (code "56") (name "unconnected-(U1A-GMII2_TXD0{slash}RGMII2_TD0{slash}RMII2_TXD0{slash}GPMC_A21{slash}PR1_MII1_RXD3{slash}EQEP1B_IN{slash}GPIO1_21{slash}GPMC_A5-PadV15)") (class "Default")
      (node (ref "U1") (pin "V15") (pinfunction "GMII2_TXD0/RGMII2_TD0/RMII2_TXD0/GPMC_A21/PR1_MII1_RXD3/EQEP1B_IN/GPIO1_21/GPMC_A5_V15") (pintype "bidirectional"))
    )
    (net (code "57") (name "unconnected-(U1A-GMII2_TXD2{slash}RGMII2_TD2{slash}MMC2_DAT2{slash}GPMC_A19{slash}PR1_MII1_TXD1{slash}EHRPWM1B{slash}GPIO1_19{slash}GPMC_A3-PadT14)") (class "Default")
      (node (ref "U1") (pin "T14") (pinfunction "GMII2_TXD2/RGMII2_TD2/MMC2_DAT2/GPMC_A19/PR1_MII1_TXD1/EHRPWM1B/GPIO1_19/GPMC_A3_T14") (pintype "bidirectional"))
    )
    (net (code "58") (name "unconnected-(U1A-GMII2_TXD3{slash}RGMII2_TD3{slash}MMC2_DAT1{slash}GPMC_A18{slash}PR1_MII1_TXD2{slash}EHRPWM1A{slash}GPIO1_18{slash}GPMC_A2-PadU14)") (class "Default")
      (node (ref "U1") (pin "U14") (pinfunction "GMII2_TXD3/RGMII2_TD3/MMC2_DAT1/GPMC_A18/PR1_MII1_TXD2/EHRPWM1A/GPIO1_18/GPMC_A2_U14") (pintype "bidirectional"))
    )
    (net (code "59") (name "unconnected-(U1A-GMII2_TXEN{slash}RGMII2_TCTL{slash}RMII2_TXEN{slash}GPMC_A16{slash}PR1_MII_MT1_CLK{slash}EHRPWM1_TRIPZONE_INPUT{slash}GPIO1_16{slash}GPMC_A0-PadR13)") (class "Default")
      (node (ref "U1") (pin "R13") (pinfunction "GMII2_TXEN/RGMII2_TCTL/RMII2_TXEN/GPMC_A16/PR1_MII_MT1_CLK/EHRPWM1_TRIPZONE_INPUT/GPIO1_16/GPMC_A0_R13") (pintype "bidirectional"))
    )
    (net (code "60") (name "unconnected-(U1A-GPIO3_7{slash}EMU0-PadC14)") (class "Default")
      (node (ref "U1") (pin "C14") (pinfunction "GPIO3_7/EMU0_C14") (pintype "passive"))
    )
    (net (code "61") (name "unconnected-(U1A-GPIO3_8{slash}EMU1-PadB14)") (class "Default")
      (node (ref "U1") (pin "B14") (pinfunction "GPIO3_8/EMU1_B14") (pintype "passive"))
    )
    (net (code "62") (name "unconnected-(U1A-LCD_DATA16{slash}MMC1_DAT7{slash}MMC2_DAT3{slash}EQEP2_STROBE{slash}PR1_ECAP0_ECAP_CAPIN_APWM_O{slash}PR1_PRU0_PRU_R31_15{slash}GPIO1_15{slash}GPMC_AD15-PadU13)") (class "Default")
      (node (ref "U1") (pin "U13") (pinfunction "LCD_DATA16/MMC1_DAT7/MMC2_DAT3/EQEP2_STROBE/PR1_ECAP0_ECAP_CAPIN_APWM_O/PR1_PRU0_PRU_R31_15/GPIO1_15/GPMC_AD15_U13") (pintype "bidirectional"))
    )
    (net (code "63") (name "unconnected-(U1A-LCD_DATA17{slash}MMC1_DAT6{slash}MMC2_DAT2{slash}EQEP2_INDEX{slash}PR1_MII0_TXD0{slash}PR1_PRU0_PRU_R31_14{slash}GPIO1_14{slash}GPMC_AD14-PadV13)") (class "Default")
      (node (ref "U1") (pin "V13") (pinfunction "LCD_DATA17/MMC1_DAT6/MMC2_DAT2/EQEP2_INDEX/PR1_MII0_TXD0/PR1_PRU0_PRU_R31_14/GPIO1_14/GPMC_AD14_V13") (pintype "bidirectional"))
    )
    (net (code "64") (name "unconnected-(U1A-LCD_DATA18{slash}MMC1_DAT5{slash}MMC2_DAT1{slash}EQEP2B_IN{slash}PR1_MII0_TXD1{slash}PR1_PRU0_PRU_R30_15{slash}GPIO1_13{slash}GPMC_AD13-PadR12)") (class "Default")
      (node (ref "U1") (pin "R12") (pinfunction "LCD_DATA18/MMC1_DAT5/MMC2_DAT1/EQEP2B_IN/PR1_MII0_TXD1/PR1_PRU0_PRU_R30_15/GPIO1_13/GPMC_AD13_R12") (pintype "bidirectional"))
    )
    (net (code "65") (name "unconnected-(U1A-LCD_DATA19{slash}MMC1_DAT4{slash}MMC2_DAT0{slash}EQEP2A_IN{slash}PR1_MII0_TXD2{slash}PR1_PRU0_PRU_R30_14{slash}GPIO1_12{slash}GPMC_AD12-PadT12)") (class "Default")
      (node (ref "U1") (pin "T12") (pinfunction "LCD_DATA19/MMC1_DAT4/MMC2_DAT0/EQEP2A_IN/PR1_MII0_TXD2/PR1_PRU0_PRU_R30_14/GPIO1_12/GPMC_AD12_T12") (pintype "bidirectional"))
    )
    (net (code "66") (name "unconnected-(U1A-LCD_DATA20{slash}MMC1_DAT3{slash}MMC2_DAT7{slash}EHRPWM0_SYNCO{slash}PR1_MII0_TXD3{slash}{slash}GPIO0_27{slash}GPMC_AD11-PadU12)") (class "Default")
      (node (ref "U1") (pin "U12") (pinfunction "LCD_DATA20/MMC1_DAT3/MMC2_DAT7/EHRPWM0_SYNCO/PR1_MII0_TXD3//GPIO0_27/GPMC_AD11_U12") (pintype "bidirectional"))
    )
    (net (code "67") (name "unconnected-(U1A-LCD_DATA21{slash}MMC1_DAT2{slash}MMC2_DAT6{slash}EHRPWM2_TRIPZONE_INPUT{slash}PR1_MII0_TXEN{slash}{slash}GPIO0_26{slash}GPMC_AD10-PadT11)") (class "Default")
      (node (ref "U1") (pin "T11") (pinfunction "LCD_DATA21/MMC1_DAT2/MMC2_DAT6/EHRPWM2_TRIPZONE_INPUT/PR1_MII0_TXEN//GPIO0_26/GPMC_AD10_T11") (pintype "bidirectional"))
    )
    (net (code "68") (name "unconnected-(U1A-LCD_DATA22{slash}MMC1_DAT1{slash}MMC2_DAT5{slash}EHRPWM2B{slash}PR1_MII0_COL{slash}{slash}GPIO0_23{slash}GPMC_AD9-PadT10)") (class "Default")
      (node (ref "U1") (pin "T10") (pinfunction "LCD_DATA22/MMC1_DAT1/MMC2_DAT5/EHRPWM2B/PR1_MII0_COL//GPIO0_23/GPMC_AD9_T10") (pintype "bidirectional"))
    )
    (net (code "69") (name "unconnected-(U1A-LCD_DATA23{slash}MMC1_DAT0{slash}MMC2_DAT4{slash}EHRPWM2A{slash}PR1_MII_MT0_CLK{slash}{slash}GPIO0_22{slash}GPMC_AD8-PadU10)") (class "Default")
      (node (ref "U1") (pin "U10") (pinfunction "LCD_DATA23/MMC1_DAT0/MMC2_DAT4/EHRPWM2A/PR1_MII_MT0_CLK//GPIO0_22/GPMC_AD8_U10") (pintype "bidirectional"))
    )
    (net (code "70") (name "unconnected-(U1A-LCD_MEMORY_CLK{slash}GPMC_WAIT1{slash}MMC2_CLK{slash}PR1_MII1_CRS{slash}PR1_MDIO_MDCLK{slash}MCASP0_FSR{slash}GPIO2_1{slash}GPMC_CLK-PadV12)") (class "Default")
      (node (ref "U1") (pin "V12") (pinfunction "LCD_MEMORY_CLK/GPMC_WAIT1/MMC2_CLK/PR1_MII1_CRS/PR1_MDIO_MDCLK/MCASP0_FSR/GPIO2_1/GPMC_CLK_V12") (pintype "bidirectional"))
    )
    (net (code "71") (name "unconnected-(U1A-MMC2_CMD{slash}PR1_MII0_CRS{slash}PR1_MDIO_DATA{slash}EMU4{slash}GPIO2_0{slash}GPMC_CSn3-PadT13)") (class "Default")
      (node (ref "U1") (pin "T13") (pinfunction "MMC2_CMD/PR1_MII0_CRS/PR1_MDIO_DATA/EMU4/GPIO2_0/GPMC_CSn3_T13") (pintype "bidirectional"))
    )
    (net (code "72") (name "unconnected-(U1A-TIMER4{slash}GPIO2_2{slash}TIMER7{slash}GPIO2_3{slash}GPMC_OEn_REn-PadT7)") (class "Default")
      (node (ref "U1") (pin "T7") (pinfunction "TIMER4/GPIO2_2/TIMER7/GPIO2_3/GPMC_OEn_REn_T7") (pintype "bidirectional"))
    )
    (net (code "73") (name "unconnected-(U1A-TIMER5{slash}GPIO2_5{slash}GPMC_BEn0_CLE-PadT6)") (class "Default")
      (node (ref "U1") (pin "T6") (pinfunction "TIMER5/GPIO2_5/GPMC_BEn0_CLE_T6") (pintype "bidirectional"))
    )
    (net (code "74") (name "unconnected-(U1A-TIMER5{slash}GPIO2_5{slash}TIMER4{slash}GPIO2_2{slash}GPMC_ADVn_ALE-PadR7)") (class "Default")
      (node (ref "U1") (pin "R7") (pinfunction "TIMER5/GPIO2_5/TIMER4/GPIO2_2/GPMC_ADVn_ALE_R7") (pintype "bidirectional"))
    )
    (net (code "75") (name "unconnected-(U1A-TIMER6{slash}GPIO2_4{slash}GPMC_WEn-PadU6)") (class "Default")
      (node (ref "U1") (pin "U6") (pinfunction "TIMER6/GPIO2_4/GPMC_WEn_U6") (pintype "bidirectional"))
    )
    (net (code "76") (name "unconnected-(U9-GND-Pad2)") (class "Default")
      (node (ref "U9") (pin "2") (pinfunction "GND_2") (pintype "power_in"))
    )
  )
)
